# alig.net
KiCad netlist of a schematic drawn in EAGLE
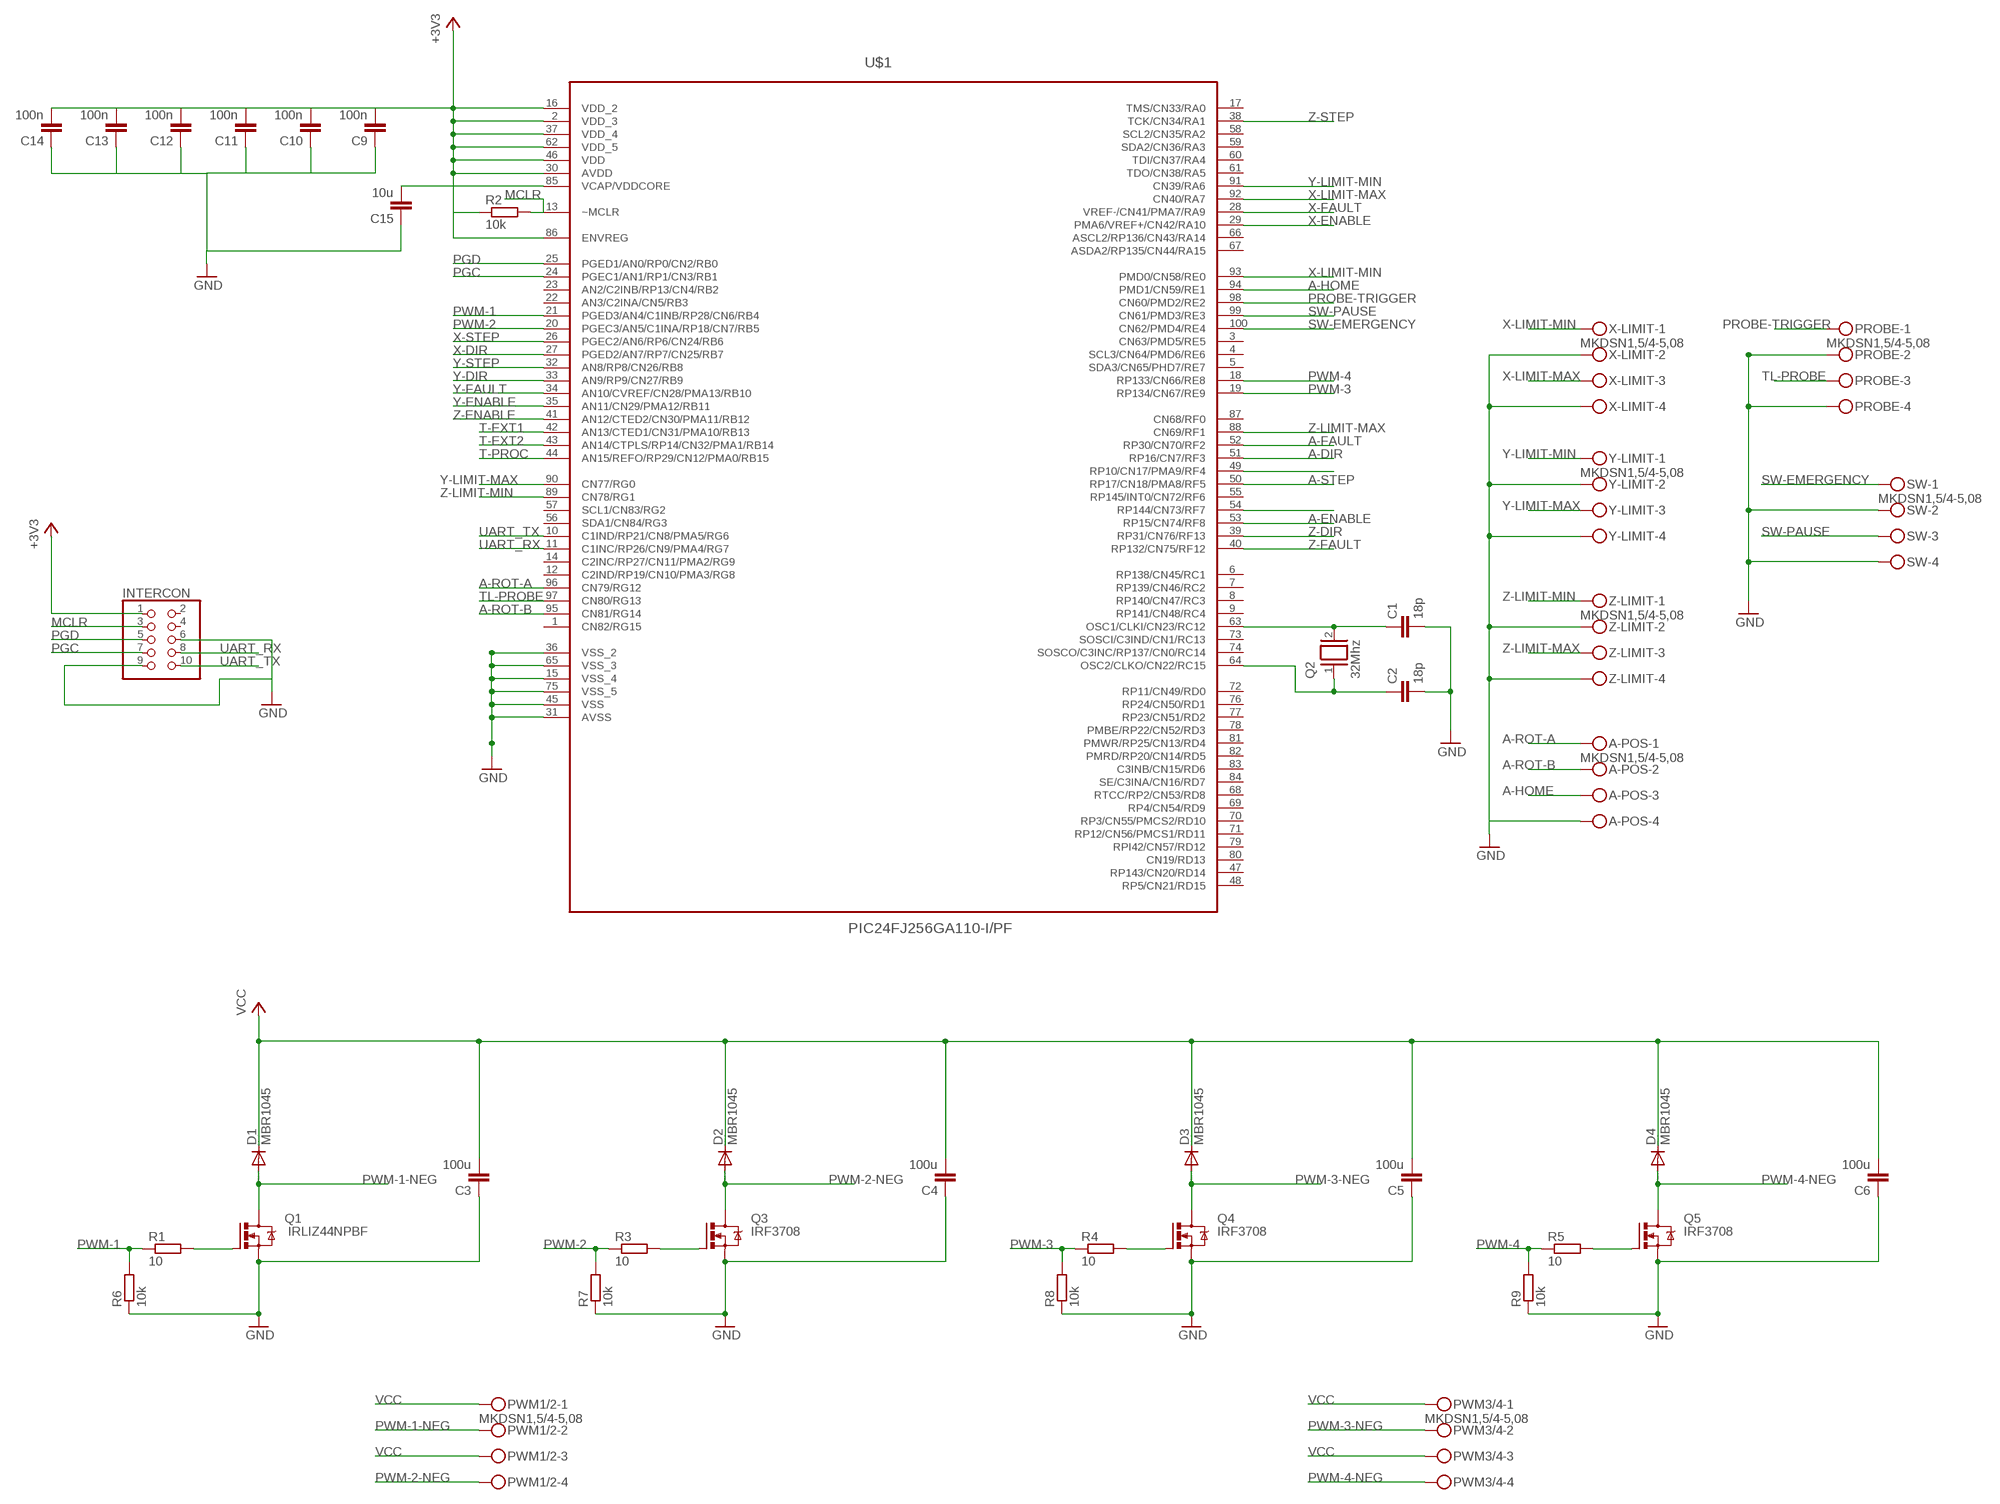
[diagram p0: schematic, sheet 1, part 1 of 3]
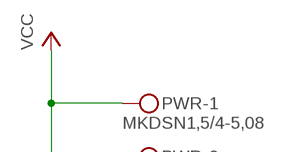
[diagram p1: schematic, sheet 1, part 2 of 3]
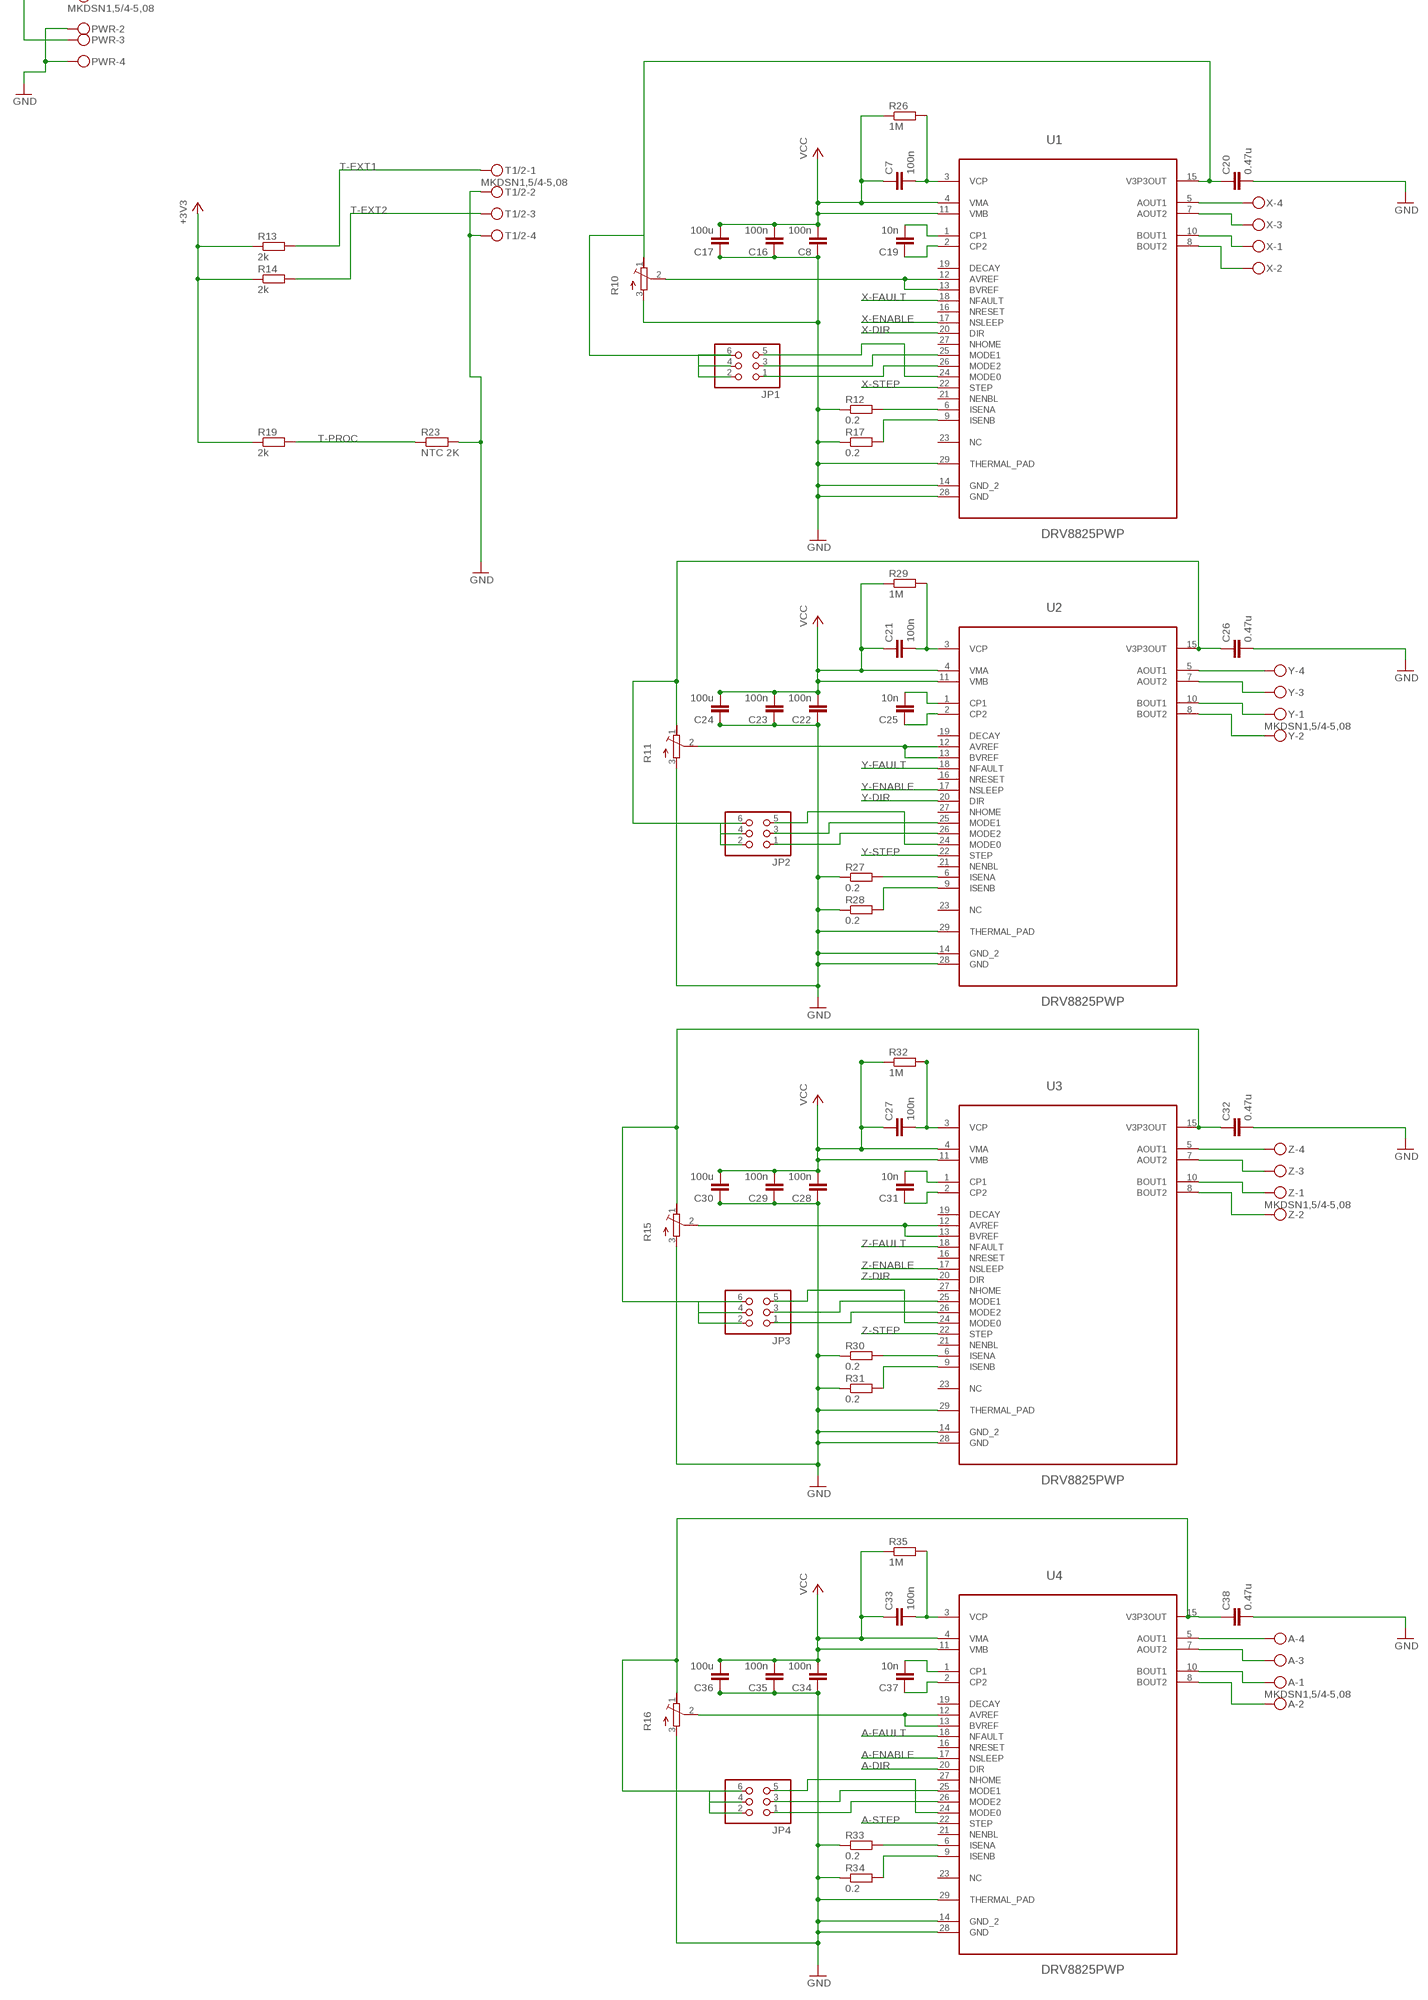
[diagram p2: schematic, sheet 1, part 3 of 3]

(export (version "E")
  (design (tool "Eeschema 10.0.6"))
  (components
    (comp (ref "A")
      (value "MKDSN1,5/4-5,08")
      (footprint "eagle-import:MKDSN1,5_4-5,08")
      (libsource (lib "eagle-import") (part "MKDSN1,5/4-5,08"))
    )
    (comp (ref "A-POS")
      (value "MKDSN1,5/4-5,08")
      (footprint "eagle-import:MKDSN1,5_4-5,08")
      (libsource (lib "eagle-import") (part "MKDSN1,5/4-5,08"))
    )
    (comp (ref "C1")
      (value "18p")
      (footprint "eagle-import:C0805")
      (libsource (lib "eagle-import") (part "C-EUC0805"))
    )
    (comp (ref "C2")
      (value "18p")
      (footprint "eagle-import:C0805")
      (libsource (lib "eagle-import") (part "C-EUC0805"))
    )
    (comp (ref "C3")
      (value "100u")
      (footprint "eagle-import:C0805")
      (libsource (lib "eagle-import") (part "C-EUC0805"))
    )
    (comp (ref "C4")
      (value "100u")
      (footprint "eagle-import:C0805")
      (libsource (lib "eagle-import") (part "C-EUC0805"))
    )
    (comp (ref "C5")
      (value "100u")
      (footprint "eagle-import:C0805")
      (libsource (lib "eagle-import") (part "C-EUC0805"))
    )
    (comp (ref "C6")
      (value "100u")
      (footprint "eagle-import:C0805")
      (libsource (lib "eagle-import") (part "C-EUC0805"))
    )
    (comp (ref "C7")
      (value "100n")
      (footprint "eagle-import:C0805")
      (libsource (lib "eagle-import") (part "C-EUC0805"))
    )
    (comp (ref "C8")
      (value "100n")
      (footprint "eagle-import:C0805")
      (libsource (lib "eagle-import") (part "C-EUC0805"))
    )
    (comp (ref "C9")
      (value "100n")
      (footprint "eagle-import:C0805")
      (libsource (lib "eagle-import") (part "C-EUC0805"))
    )
    (comp (ref "C10")
      (value "100n")
      (footprint "eagle-import:C0805")
      (libsource (lib "eagle-import") (part "C-EUC0805"))
    )
    (comp (ref "C11")
      (value "100n")
      (footprint "eagle-import:C0805")
      (libsource (lib "eagle-import") (part "C-EUC0805"))
    )
    (comp (ref "C12")
      (value "100n")
      (footprint "eagle-import:C0805")
      (libsource (lib "eagle-import") (part "C-EUC0805"))
    )
    (comp (ref "C13")
      (value "100n")
      (footprint "eagle-import:C0805")
      (libsource (lib "eagle-import") (part "C-EUC0805"))
    )
    (comp (ref "C14")
      (value "100n")
      (footprint "eagle-import:C0805")
      (libsource (lib "eagle-import") (part "C-EUC0805"))
    )
    (comp (ref "C15")
      (value "10u")
      (footprint "eagle-import:C0805")
      (libsource (lib "eagle-import") (part "C-EUC0805"))
    )
    (comp (ref "C16")
      (value "100n")
      (footprint "eagle-import:C0805")
      (libsource (lib "eagle-import") (part "C-EUC0805"))
    )
    (comp (ref "C17")
      (value "100u")
      (footprint "eagle-import:C0805")
      (libsource (lib "eagle-import") (part "C-EUC0805"))
    )
    (comp (ref "C19")
      (value "10n")
      (footprint "eagle-import:C0805")
      (libsource (lib "eagle-import") (part "C-EUC0805"))
    )
    (comp (ref "C20")
      (value "0.47u")
      (footprint "eagle-import:C0805")
      (libsource (lib "eagle-import") (part "C-EUC0805"))
    )
    (comp (ref "C21")
      (value "100n")
      (footprint "eagle-import:C0805")
      (libsource (lib "eagle-import") (part "C-EUC0805"))
    )
    (comp (ref "C22")
      (value "100n")
      (footprint "eagle-import:C0805")
      (libsource (lib "eagle-import") (part "C-EUC0805"))
    )
    (comp (ref "C23")
      (value "100n")
      (footprint "eagle-import:C0805")
      (libsource (lib "eagle-import") (part "C-EUC0805"))
    )
    (comp (ref "C24")
      (value "100u")
      (footprint "eagle-import:C0805")
      (libsource (lib "eagle-import") (part "C-EUC0805"))
    )
    (comp (ref "C25")
      (value "10n")
      (footprint "eagle-import:C0805")
      (libsource (lib "eagle-import") (part "C-EUC0805"))
    )
    (comp (ref "C26")
      (value "0.47u")
      (footprint "eagle-import:C0805")
      (libsource (lib "eagle-import") (part "C-EUC0805"))
    )
    (comp (ref "C27")
      (value "100n")
      (footprint "eagle-import:C0805")
      (libsource (lib "eagle-import") (part "C-EUC0805"))
    )
    (comp (ref "C28")
      (value "100n")
      (footprint "eagle-import:C0805")
      (libsource (lib "eagle-import") (part "C-EUC0805"))
    )
    (comp (ref "C29")
      (value "100n")
      (footprint "eagle-import:C0805")
      (libsource (lib "eagle-import") (part "C-EUC0805"))
    )
    (comp (ref "C30")
      (value "100u")
      (footprint "eagle-import:C0805")
      (libsource (lib "eagle-import") (part "C-EUC0805"))
    )
    (comp (ref "C31")
      (value "10n")
      (footprint "eagle-import:C0805")
      (libsource (lib "eagle-import") (part "C-EUC0805"))
    )
    (comp (ref "C32")
      (value "0.47u")
      (footprint "eagle-import:C0805")
      (libsource (lib "eagle-import") (part "C-EUC0805"))
    )
    (comp (ref "C33")
      (value "100n")
      (footprint "eagle-import:C0805")
      (libsource (lib "eagle-import") (part "C-EUC0805"))
    )
    (comp (ref "C34")
      (value "100n")
      (footprint "eagle-import:C0805")
      (libsource (lib "eagle-import") (part "C-EUC0805"))
    )
    (comp (ref "C35")
      (value "100n")
      (footprint "eagle-import:C0805")
      (libsource (lib "eagle-import") (part "C-EUC0805"))
    )
    (comp (ref "C36")
      (value "100u")
      (footprint "eagle-import:C0805")
      (libsource (lib "eagle-import") (part "C-EUC0805"))
    )
    (comp (ref "C37")
      (value "10n")
      (footprint "eagle-import:C0805")
      (libsource (lib "eagle-import") (part "C-EUC0805"))
    )
    (comp (ref "C38")
      (value "0.47u")
      (footprint "eagle-import:C0805")
      (libsource (lib "eagle-import") (part "C-EUC0805"))
    )
    (comp (ref "D1")
      (value "MBR1045")
      (footprint "eagle-import:TO220ACS")
      (libsource (lib "eagle-import") (part "BYT08P"))
    )
    (comp (ref "D2")
      (value "MBR1045")
      (footprint "eagle-import:TO220ACS")
      (libsource (lib "eagle-import") (part "BYT08P"))
    )
    (comp (ref "D3")
      (value "MBR1045")
      (footprint "eagle-import:TO220ACS")
      (libsource (lib "eagle-import") (part "BYT08P"))
    )
    (comp (ref "D4")
      (value "MBR1045")
      (footprint "eagle-import:TO220ACS")
      (libsource (lib "eagle-import") (part "BYT08P"))
    )
    (comp (ref "INTERCON")
      (value "PINHD-2X5")
      (footprint "eagle-import:2X05")
      (libsource (lib "eagle-import") (part "PINHD-2X5"))
    )
    (comp (ref "JP1")
      (value "PINHD-2X3")
      (footprint "eagle-import:2X03")
      (libsource (lib "eagle-import") (part "PINHD-2X3"))
    )
    (comp (ref "JP2")
      (value "PINHD-2X3")
      (footprint "eagle-import:2X03")
      (libsource (lib "eagle-import") (part "PINHD-2X3"))
    )
    (comp (ref "JP3")
      (value "PINHD-2X3")
      (footprint "eagle-import:2X03")
      (libsource (lib "eagle-import") (part "PINHD-2X3"))
    )
    (comp (ref "JP4")
      (value "PINHD-2X3")
      (footprint "eagle-import:2X03")
      (libsource (lib "eagle-import") (part "PINHD-2X3"))
    )
    (comp (ref "PROBE")
      (value "MKDSN1,5/4-5,08")
      (footprint "eagle-import:MKDSN1,5_4-5,08")
      (libsource (lib "eagle-import") (part "MKDSN1,5/4-5,08"))
    )
    (comp (ref "PWM1/2")
      (value "MKDSN1,5/4-5,08")
      (footprint "eagle-import:MKDSN1,5_4-5,08")
      (libsource (lib "eagle-import") (part "MKDSN1,5/4-5,08"))
    )
    (comp (ref "PWM3/4")
      (value "MKDSN1,5/4-5,08")
      (footprint "eagle-import:MKDSN1,5_4-5,08")
      (libsource (lib "eagle-import") (part "MKDSN1,5/4-5,08"))
    )
    (comp (ref "PWR")
      (value "MKDSN1,5/4-5,08")
      (footprint "eagle-import:MKDSN1,5_4-5,08")
      (libsource (lib "eagle-import") (part "MKDSN1,5/4-5,08"))
    )
    (comp (ref "Q1")
      (value "IRLIZ44NPBF")
      (footprint "eagle-import:TO220BV")
      (libsource (lib "eagle-import") (part "IRF540"))
    )
    (comp (ref "Q2")
      (value "32Mhz")
      (footprint "eagle-import:QS")
      (libsource (lib "eagle-import") (part "XTAL/S"))
    )
    (comp (ref "Q3")
      (value "IRF3708")
      (footprint "eagle-import:TO220BV")
      (libsource (lib "eagle-import") (part "IRF540"))
    )
    (comp (ref "Q4")
      (value "IRF3708")
      (footprint "eagle-import:TO220BV")
      (libsource (lib "eagle-import") (part "IRF540"))
    )
    (comp (ref "Q5")
      (value "IRF3708")
      (footprint "eagle-import:TO220BV")
      (libsource (lib "eagle-import") (part "IRF540"))
    )
    (comp (ref "R1")
      (value "10")
      (footprint "eagle-import:R0805")
      (libsource (lib "eagle-import") (part "resistor_R-EU_R0805"))
    )
    (comp (ref "R2")
      (value "10k")
      (footprint "eagle-import:R0805")
      (libsource (lib "eagle-import") (part "resistor_R-EU_R0805"))
    )
    (comp (ref "R3")
      (value "10")
      (footprint "eagle-import:R0805")
      (libsource (lib "eagle-import") (part "resistor_R-EU_R0805"))
    )
    (comp (ref "R4")
      (value "10")
      (footprint "eagle-import:R0805")
      (libsource (lib "eagle-import") (part "resistor_R-EU_R0805"))
    )
    (comp (ref "R5")
      (value "10")
      (footprint "eagle-import:R0805")
      (libsource (lib "eagle-import") (part "resistor_R-EU_R0805"))
    )
    (comp (ref "R6")
      (value "10k")
      (footprint "eagle-import:R0805")
      (libsource (lib "eagle-import") (part "resistor_R-EU_R0805"))
    )
    (comp (ref "R7")
      (value "10k")
      (footprint "eagle-import:R0805")
      (libsource (lib "eagle-import") (part "resistor_R-EU_R0805"))
    )
    (comp (ref "R8")
      (value "10k")
      (footprint "eagle-import:R0805")
      (libsource (lib "eagle-import") (part "resistor_R-EU_R0805"))
    )
    (comp (ref "R9")
      (value "10k")
      (footprint "eagle-import:R0805")
      (libsource (lib "eagle-import") (part "resistor_R-EU_R0805"))
    )
    (comp (ref "R10")
      (value "R-TRIMM3314J")
      (footprint "eagle-import:RTRIM3314J")
      (libsource (lib "eagle-import") (part "R-TRIMM3314J"))
    )
    (comp (ref "R11")
      (value "R-TRIMM3314J")
      (footprint "eagle-import:RTRIM3314J")
      (libsource (lib "eagle-import") (part "R-TRIMM3314J"))
    )
    (comp (ref "R12")
      (value "0.2")
      (footprint "eagle-import:R1206")
      (libsource (lib "eagle-import") (part "R-EU_R1206"))
    )
    (comp (ref "R13")
      (value "2k")
      (footprint "eagle-import:R0805")
      (libsource (lib "eagle-import") (part "resistor_R-EU_R0805"))
    )
    (comp (ref "R14")
      (value "2k")
      (footprint "eagle-import:R0805")
      (libsource (lib "eagle-import") (part "resistor_R-EU_R0805"))
    )
    (comp (ref "R15")
      (value "R-TRIMM3314J")
      (footprint "eagle-import:RTRIM3314J")
      (libsource (lib "eagle-import") (part "R-TRIMM3314J"))
    )
    (comp (ref "R16")
      (value "R-TRIMM3314J")
      (footprint "eagle-import:RTRIM3314J")
      (libsource (lib "eagle-import") (part "R-TRIMM3314J"))
    )
    (comp (ref "R17")
      (value "0.2")
      (footprint "eagle-import:R1206")
      (libsource (lib "eagle-import") (part "R-EU_R1206"))
    )
    (comp (ref "R19")
      (value "2k")
      (footprint "eagle-import:R0805")
      (libsource (lib "eagle-import") (part "resistor_R-EU_R0805"))
    )
    (comp (ref "R23")
      (value "NTC 2K")
      (footprint "eagle-import:R0805")
      (libsource (lib "eagle-import") (part "resistor_R-EU_R0805"))
    )
    (comp (ref "R26")
      (value "1M")
      (footprint "eagle-import:R0805")
      (libsource (lib "eagle-import") (part "resistor_R-EU_R0805"))
    )
    (comp (ref "R27")
      (value "0.2")
      (footprint "eagle-import:R1206")
      (libsource (lib "eagle-import") (part "R-EU_R1206"))
    )
    (comp (ref "R28")
      (value "0.2")
      (footprint "eagle-import:R1206")
      (libsource (lib "eagle-import") (part "R-EU_R1206"))
    )
    (comp (ref "R29")
      (value "1M")
      (footprint "eagle-import:R0805")
      (libsource (lib "eagle-import") (part "resistor_R-EU_R0805"))
    )
    (comp (ref "R30")
      (value "0.2")
      (footprint "eagle-import:R1206")
      (libsource (lib "eagle-import") (part "R-EU_R1206"))
    )
    (comp (ref "R31")
      (value "0.2")
      (footprint "eagle-import:R1206")
      (libsource (lib "eagle-import") (part "R-EU_R1206"))
    )
    (comp (ref "R32")
      (value "1M")
      (footprint "eagle-import:R0805")
      (libsource (lib "eagle-import") (part "resistor_R-EU_R0805"))
    )
    (comp (ref "R33")
      (value "0.2")
      (footprint "eagle-import:R1206")
      (libsource (lib "eagle-import") (part "R-EU_R1206"))
    )
    (comp (ref "R34")
      (value "0.2")
      (footprint "eagle-import:R1206")
      (libsource (lib "eagle-import") (part "R-EU_R1206"))
    )
    (comp (ref "R35")
      (value "1M")
      (footprint "eagle-import:R0805")
      (libsource (lib "eagle-import") (part "resistor_R-EU_R0805"))
    )
    (comp (ref "SW")
      (value "MKDSN1,5/4-5,08")
      (footprint "eagle-import:MKDSN1,5_4-5,08")
      (libsource (lib "eagle-import") (part "MKDSN1,5/4-5,08"))
    )
    (comp (ref "T1/2")
      (value "MKDSN1,5/4-5,08")
      (footprint "eagle-import:MKDSN1,5_4-5,08")
      (libsource (lib "eagle-import") (part "MKDSN1,5/4-5,08"))
    )
    (comp (ref "U$1")
      (value "PIC24FJ256GA110-I/PF")
      (footprint "eagle-import:QFP50P1600X1600X120-100N")
      (libsource (lib "eagle-import") (part "PIC24FJ256GA110-I/PF"))
    )
    (comp (ref "U1")
      (value "DRV8825PWP")
      (footprint "eagle-import:SOP65P640X120-29N")
      (libsource (lib "eagle-import") (part "DRV8825PWP"))
    )
    (comp (ref "U2")
      (value "DRV8825PWP")
      (footprint "eagle-import:SOP65P640X120-29N")
      (libsource (lib "eagle-import") (part "DRV8825PWP"))
    )
    (comp (ref "U3")
      (value "DRV8825PWP")
      (footprint "eagle-import:SOP65P640X120-29N")
      (libsource (lib "eagle-import") (part "DRV8825PWP"))
    )
    (comp (ref "U4")
      (value "DRV8825PWP")
      (footprint "eagle-import:SOP65P640X120-29N")
      (libsource (lib "eagle-import") (part "DRV8825PWP"))
    )
    (comp (ref "X")
      (value "MKDSN1,5/4-5,08")
      (footprint "eagle-import:MKDSN1,5_4-5,08")
      (libsource (lib "eagle-import") (part "MKDSN1,5/4-5,08"))
    )
    (comp (ref "X-LIMIT")
      (value "MKDSN1,5/4-5,08")
      (footprint "eagle-import:MKDSN1,5_4-5,08")
      (libsource (lib "eagle-import") (part "MKDSN1,5/4-5,08"))
    )
    (comp (ref "Y")
      (value "MKDSN1,5/4-5,08")
      (footprint "eagle-import:MKDSN1,5_4-5,08")
      (libsource (lib "eagle-import") (part "MKDSN1,5/4-5,08"))
    )
    (comp (ref "Y-LIMIT")
      (value "MKDSN1,5/4-5,08")
      (footprint "eagle-import:MKDSN1,5_4-5,08")
      (libsource (lib "eagle-import") (part "MKDSN1,5/4-5,08"))
    )
    (comp (ref "Z")
      (value "MKDSN1,5/4-5,08")
      (footprint "eagle-import:MKDSN1,5_4-5,08")
      (libsource (lib "eagle-import") (part "MKDSN1,5/4-5,08"))
    )
    (comp (ref "Z-LIMIT")
      (value "MKDSN1,5/4-5,08")
      (footprint "eagle-import:MKDSN1,5_4-5,08")
      (libsource (lib "eagle-import") (part "MKDSN1,5/4-5,08"))
    )
  )
  (nets
    (net (code "1") (name "+3V3") (class "Default")
      (node (ref "C10") (pin "2") (pinfunction "2_2") (pintype "passive"))
      (node (ref "C11") (pin "2") (pinfunction "2_2") (pintype "passive"))
      (node (ref "C12") (pin "2") (pinfunction "2_2") (pintype "passive"))
      (node (ref "C13") (pin "2") (pinfunction "2_2") (pintype "passive"))
      (node (ref "C14") (pin "2") (pinfunction "2_2") (pintype "passive"))
      (node (ref "C9") (pin "2") (pinfunction "2_2") (pintype "passive"))
      (node (ref "INTERCON") (pin "1") (pinfunction "1_1") (pintype "passive"))
      (node (ref "R13") (pin "1") (pinfunction "1_1") (pintype "passive"))
      (node (ref "R14") (pin "1") (pinfunction "1_1") (pintype "passive"))
      (node (ref "R19") (pin "1") (pinfunction "1_1") (pintype "passive"))
      (node (ref "R2") (pin "1") (pinfunction "1_1") (pintype "passive"))
      (node (ref "U$1") (pin "16") (pinfunction "VDD_2_16") (pintype "power_in"))
      (node (ref "U$1") (pin "2") (pinfunction "VDD_3_2") (pintype "power_in"))
      (node (ref "U$1") (pin "30") (pinfunction "AVDD_30") (pintype "power_in"))
      (node (ref "U$1") (pin "37") (pinfunction "VDD_4_37") (pintype "power_in"))
      (node (ref "U$1") (pin "46") (pinfunction "VDD_46") (pintype "power_in"))
      (node (ref "U$1") (pin "62") (pinfunction "VDD_5_62") (pintype "power_in"))
      (node (ref "U$1") (pin "86") (pinfunction "ENVREG_86") (pintype "input"))
    )
    (net (code "2") (name "/A-DIR") (class "Default")
      (node (ref "U$1") (pin "51") (pinfunction "RP16/CN7/RF3_51") (pintype "bidirectional"))
      (node (ref "U4") (pin "20") (pinfunction "DIR_20") (pintype "input"))
    )
    (net (code "3") (name "/A-ENABLE") (class "Default")
      (node (ref "U$1") (pin "53") (pinfunction "RP15/CN74/RF8_53") (pintype "bidirectional"))
      (node (ref "U4") (pin "17") (pinfunction "NSLEEP_17") (pintype "input"))
    )
    (net (code "4") (name "/A-FAULT") (class "Default")
      (node (ref "U$1") (pin "52") (pinfunction "RP30/CN70/RF2_52") (pintype "bidirectional"))
      (node (ref "U4") (pin "18") (pinfunction "NFAULT_18") (pintype "input"))
    )
    (net (code "5") (name "/A-HOME") (class "Default")
      (node (ref "A-POS") (pin "3") (pinfunction "KL_3") (pintype "passive"))
      (node (ref "U$1") (pin "94") (pinfunction "PMD1/CN59/RE1_94") (pintype "bidirectional"))
    )
    (net (code "6") (name "/A-ROT-A") (class "Default")
      (node (ref "A-POS") (pin "1") (pinfunction "KL_1") (pintype "passive"))
      (node (ref "U$1") (pin "96") (pinfunction "CN79/RG12_96") (pintype "bidirectional"))
    )
    (net (code "7") (name "/A-ROT-B") (class "Default")
      (node (ref "A-POS") (pin "2") (pinfunction "KL_2") (pintype "passive"))
      (node (ref "U$1") (pin "95") (pinfunction "CN81/RG14_95") (pintype "bidirectional"))
    )
    (net (code "8") (name "/A-STEP") (class "Default")
      (node (ref "U$1") (pin "50") (pinfunction "RP17/CN18/PMA8/RF5_50") (pintype "bidirectional"))
      (node (ref "U4") (pin "22") (pinfunction "STEP_22") (pintype "input"))
    )
    (net (code "9") (name "/MCLR") (class "Default")
      (node (ref "INTERCON") (pin "3") (pinfunction "3_3") (pintype "passive"))
      (node (ref "R2") (pin "2") (pinfunction "2_2") (pintype "passive"))
      (node (ref "U$1") (pin "13") (pinfunction "~{MCLR}_13") (pintype "input"))
    )
    (net (code "10") (name "/PGC") (class "Default")
      (node (ref "INTERCON") (pin "7") (pinfunction "7_7") (pintype "passive"))
      (node (ref "U$1") (pin "24") (pinfunction "PGEC1/AN1/RP1/CN3/RB1_24") (pintype "bidirectional"))
    )
    (net (code "11") (name "/PGD") (class "Default")
      (node (ref "INTERCON") (pin "5") (pinfunction "5_5") (pintype "passive"))
      (node (ref "U$1") (pin "25") (pinfunction "PGED1/AN0/RP0/CN2/RB0_25") (pintype "bidirectional"))
    )
    (net (code "12") (name "/PROBE-TRIGGER") (class "Default")
      (node (ref "PROBE") (pin "1") (pinfunction "KL_1") (pintype "passive"))
      (node (ref "U$1") (pin "98") (pinfunction "CN60/PMD2/RE2_98") (pintype "bidirectional"))
    )
    (net (code "13") (name "/PWM-1") (class "Default")
      (node (ref "R1") (pin "1") (pinfunction "1_1") (pintype "passive"))
      (node (ref "R6") (pin "2") (pinfunction "2_2") (pintype "passive"))
      (node (ref "U$1") (pin "21") (pinfunction "PGED3/AN4/C1INB/RP28/CN6/RB4_21") (pintype "bidirectional"))
    )
    (net (code "14") (name "/PWM-1-NEG") (class "Default")
      (node (ref "D1") (pin "A") (pinfunction "A_A") (pintype "passive"))
      (node (ref "PWM1/2") (pin "2") (pinfunction "KL_2") (pintype "passive"))
      (node (ref "Q1") (pin "D") (pinfunction "D_D") (pintype "passive"))
    )
    (net (code "15") (name "/PWM-2") (class "Default")
      (node (ref "R3") (pin "1") (pinfunction "1_1") (pintype "passive"))
      (node (ref "R7") (pin "2") (pinfunction "2_2") (pintype "passive"))
      (node (ref "U$1") (pin "20") (pinfunction "PGEC3/AN5/C1INA/RP18/CN7/RB5_20") (pintype "bidirectional"))
    )
    (net (code "16") (name "/PWM-2-NEG") (class "Default")
      (node (ref "D2") (pin "A") (pinfunction "A_A") (pintype "passive"))
      (node (ref "PWM1/2") (pin "4") (pinfunction "KL_4") (pintype "passive"))
      (node (ref "Q3") (pin "D") (pinfunction "D_D") (pintype "passive"))
    )
    (net (code "17") (name "/PWM-3") (class "Default")
      (node (ref "R4") (pin "1") (pinfunction "1_1") (pintype "passive"))
      (node (ref "R8") (pin "2") (pinfunction "2_2") (pintype "passive"))
      (node (ref "U$1") (pin "19") (pinfunction "RP134/CN67/RE9_19") (pintype "bidirectional"))
    )
    (net (code "18") (name "/PWM-3-NEG") (class "Default")
      (node (ref "D3") (pin "A") (pinfunction "A_A") (pintype "passive"))
      (node (ref "PWM3/4") (pin "2") (pinfunction "KL_2") (pintype "passive"))
      (node (ref "Q4") (pin "D") (pinfunction "D_D") (pintype "passive"))
    )
    (net (code "19") (name "/PWM-4") (class "Default")
      (node (ref "R5") (pin "1") (pinfunction "1_1") (pintype "passive"))
      (node (ref "R9") (pin "2") (pinfunction "2_2") (pintype "passive"))
      (node (ref "U$1") (pin "18") (pinfunction "RP133/CN66/RE8_18") (pintype "bidirectional"))
    )
    (net (code "20") (name "/PWM-4-NEG") (class "Default")
      (node (ref "D4") (pin "A") (pinfunction "A_A") (pintype "passive"))
      (node (ref "PWM3/4") (pin "4") (pinfunction "KL_4") (pintype "passive"))
      (node (ref "Q5") (pin "D") (pinfunction "D_D") (pintype "passive"))
    )
    (net (code "21") (name "/SW-EMERGENCY") (class "Default")
      (node (ref "SW") (pin "1") (pinfunction "KL_1") (pintype "passive"))
      (node (ref "U$1") (pin "100") (pinfunction "CN62/PMD4/RE4_100") (pintype "bidirectional"))
    )
    (net (code "22") (name "/SW-PAUSE") (class "Default")
      (node (ref "SW") (pin "3") (pinfunction "KL_3") (pintype "passive"))
      (node (ref "U$1") (pin "99") (pinfunction "CN61/PMD3/RE3_99") (pintype "bidirectional"))
    )
    (net (code "23") (name "/T-EXT1") (class "Default")
      (node (ref "R13") (pin "2") (pinfunction "2_2") (pintype "passive"))
      (node (ref "T1/2") (pin "1") (pinfunction "KL_1") (pintype "passive"))
      (node (ref "U$1") (pin "42") (pinfunction "AN13/CTED1/CN31/PMA10/RB13_42") (pintype "bidirectional"))
    )
    (net (code "24") (name "/T-EXT2") (class "Default")
      (node (ref "R14") (pin "2") (pinfunction "2_2") (pintype "passive"))
      (node (ref "T1/2") (pin "3") (pinfunction "KL_3") (pintype "passive"))
      (node (ref "U$1") (pin "43") (pinfunction "AN14/CTPLS/RP14/CN32/PMA1/RB14_43") (pintype "bidirectional"))
    )
    (net (code "25") (name "/T-PROC") (class "Default")
      (node (ref "R19") (pin "2") (pinfunction "2_2") (pintype "passive"))
      (node (ref "R23") (pin "1") (pinfunction "1_1") (pintype "passive"))
      (node (ref "U$1") (pin "44") (pinfunction "AN15/REFO/RP29/CN12/PMA0/RB15_44") (pintype "bidirectional"))
    )
    (net (code "26") (name "/TL-PROBE") (class "Default")
      (node (ref "PROBE") (pin "3") (pinfunction "KL_3") (pintype "passive"))
      (node (ref "U$1") (pin "97") (pinfunction "CN80/RG13_97") (pintype "bidirectional"))
    )
    (net (code "27") (name "/UART_RX") (class "Default")
      (node (ref "INTERCON") (pin "8") (pinfunction "8_8") (pintype "passive"))
      (node (ref "U$1") (pin "11") (pinfunction "C1INC/RP26/CN9/PMA4/RG7_11") (pintype "bidirectional"))
    )
    (net (code "28") (name "/UART_TX") (class "Default")
      (node (ref "INTERCON") (pin "10") (pinfunction "10_10") (pintype "passive"))
      (node (ref "U$1") (pin "10") (pinfunction "C1IND/RP21/CN8/PMA5/RG6_10") (pintype "bidirectional"))
    )
    (net (code "29") (name "/X-DIR") (class "Default")
      (node (ref "U$1") (pin "27") (pinfunction "PGED2/AN7/RP7/CN25/RB7_27") (pintype "bidirectional"))
      (node (ref "U1") (pin "20") (pinfunction "DIR_20") (pintype "input"))
    )
    (net (code "30") (name "/X-ENABLE") (class "Default")
      (node (ref "U$1") (pin "29") (pinfunction "PMA6/VREF+/CN42/RA10_29") (pintype "bidirectional"))
      (node (ref "U1") (pin "17") (pinfunction "NSLEEP_17") (pintype "input"))
    )
    (net (code "31") (name "/X-FAULT") (class "Default")
      (node (ref "U$1") (pin "28") (pinfunction "VREF-/CN41/PMA7/RA9_28") (pintype "bidirectional"))
      (node (ref "U1") (pin "18") (pinfunction "NFAULT_18") (pintype "input"))
    )
    (net (code "32") (name "/X-LIMIT-MAX") (class "Default")
      (node (ref "U$1") (pin "92") (pinfunction "CN40/RA7_92") (pintype "bidirectional"))
      (node (ref "X-LIMIT") (pin "3") (pinfunction "KL_3") (pintype "passive"))
    )
    (net (code "33") (name "/X-LIMIT-MIN") (class "Default")
      (node (ref "U$1") (pin "93") (pinfunction "PMD0/CN58/RE0_93") (pintype "bidirectional"))
      (node (ref "X-LIMIT") (pin "1") (pinfunction "KL_1") (pintype "passive"))
    )
    (net (code "34") (name "/X-STEP") (class "Default")
      (node (ref "U$1") (pin "26") (pinfunction "PGEC2/AN6/RP6/CN24/RB6_26") (pintype "bidirectional"))
      (node (ref "U1") (pin "22") (pinfunction "STEP_22") (pintype "input"))
    )
    (net (code "35") (name "/Y-DIR") (class "Default")
      (node (ref "U$1") (pin "33") (pinfunction "AN9/RP9/CN27/RB9_33") (pintype "bidirectional"))
      (node (ref "U2") (pin "20") (pinfunction "DIR_20") (pintype "input"))
    )
    (net (code "36") (name "/Y-ENABLE") (class "Default")
      (node (ref "U$1") (pin "35") (pinfunction "AN11/CN29/PMA12/RB11_35") (pintype "bidirectional"))
      (node (ref "U2") (pin "17") (pinfunction "NSLEEP_17") (pintype "input"))
    )
    (net (code "37") (name "/Y-FAULT") (class "Default")
      (node (ref "U$1") (pin "34") (pinfunction "AN10/CVREF/CN28/PMA13/RB10_34") (pintype "bidirectional"))
      (node (ref "U2") (pin "18") (pinfunction "NFAULT_18") (pintype "input"))
    )
    (net (code "38") (name "/Y-LIMIT-MAX") (class "Default")
      (node (ref "U$1") (pin "90") (pinfunction "CN77/RG0_90") (pintype "bidirectional"))
      (node (ref "Y-LIMIT") (pin "3") (pinfunction "KL_3") (pintype "passive"))
    )
    (net (code "39") (name "/Y-LIMIT-MIN") (class "Default")
      (node (ref "U$1") (pin "91") (pinfunction "CN39/RA6_91") (pintype "bidirectional"))
      (node (ref "Y-LIMIT") (pin "1") (pinfunction "KL_1") (pintype "passive"))
    )
    (net (code "40") (name "/Y-STEP") (class "Default")
      (node (ref "U$1") (pin "32") (pinfunction "AN8/RP8/CN26/RB8_32") (pintype "bidirectional"))
      (node (ref "U2") (pin "22") (pinfunction "STEP_22") (pintype "input"))
    )
    (net (code "41") (name "/Z-DIR") (class "Default")
      (node (ref "U$1") (pin "39") (pinfunction "RP31/CN76/RF13_39") (pintype "bidirectional"))
      (node (ref "U3") (pin "20") (pinfunction "DIR_20") (pintype "input"))
    )
    (net (code "42") (name "/Z-ENABLE") (class "Default")
      (node (ref "U$1") (pin "41") (pinfunction "AN12/CTED2/CN30/PMA11/RB12_41") (pintype "bidirectional"))
      (node (ref "U3") (pin "17") (pinfunction "NSLEEP_17") (pintype "input"))
    )
    (net (code "43") (name "/Z-FAULT") (class "Default")
      (node (ref "U$1") (pin "40") (pinfunction "RP132/CN75/RF12_40") (pintype "bidirectional"))
      (node (ref "U3") (pin "18") (pinfunction "NFAULT_18") (pintype "input"))
    )
    (net (code "44") (name "/Z-LIMIT-MAX") (class "Default")
      (node (ref "U$1") (pin "88") (pinfunction "CN69/RF1_88") (pintype "bidirectional"))
      (node (ref "Z-LIMIT") (pin "3") (pinfunction "KL_3") (pintype "passive"))
    )
    (net (code "45") (name "/Z-LIMIT-MIN") (class "Default")
      (node (ref "U$1") (pin "89") (pinfunction "CN78/RG1_89") (pintype "bidirectional"))
      (node (ref "Z-LIMIT") (pin "1") (pinfunction "KL_1") (pintype "passive"))
    )
    (net (code "46") (name "/Z-STEP") (class "Default")
      (node (ref "U$1") (pin "38") (pinfunction "TCK/CN34/RA1_38") (pintype "bidirectional"))
      (node (ref "U3") (pin "22") (pinfunction "STEP_22") (pintype "input"))
    )
    (net (code "47") (name "GND") (class "Default")
      (node (ref "A-POS") (pin "4") (pinfunction "KL_4") (pintype "passive"))
      (node (ref "C1") (pin "2") (pinfunction "2_2") (pintype "passive"))
      (node (ref "C10") (pin "1") (pinfunction "1_1") (pintype "passive"))
      (node (ref "C11") (pin "1") (pinfunction "1_1") (pintype "passive"))
      (node (ref "C12") (pin "1") (pinfunction "1_1") (pintype "passive"))
      (node (ref "C13") (pin "1") (pinfunction "1_1") (pintype "passive"))
      (node (ref "C14") (pin "1") (pinfunction "1_1") (pintype "passive"))
      (node (ref "C15") (pin "1") (pinfunction "1_1") (pintype "passive"))
      (node (ref "C16") (pin "1") (pinfunction "1_1") (pintype "passive"))
      (node (ref "C17") (pin "1") (pinfunction "1_1") (pintype "passive"))
      (node (ref "C2") (pin "2") (pinfunction "2_2") (pintype "passive"))
      (node (ref "C20") (pin "2") (pinfunction "2_2") (pintype "passive"))
      (node (ref "C22") (pin "1") (pinfunction "1_1") (pintype "passive"))
      (node (ref "C23") (pin "1") (pinfunction "1_1") (pintype "passive"))
      (node (ref "C24") (pin "1") (pinfunction "1_1") (pintype "passive"))
      (node (ref "C26") (pin "2") (pinfunction "2_2") (pintype "passive"))
      (node (ref "C28") (pin "1") (pinfunction "1_1") (pintype "passive"))
      (node (ref "C29") (pin "1") (pinfunction "1_1") (pintype "passive"))
      (node (ref "C3") (pin "1") (pinfunction "1_1") (pintype "passive"))
      (node (ref "C30") (pin "1") (pinfunction "1_1") (pintype "passive"))
      (node (ref "C32") (pin "2") (pinfunction "2_2") (pintype "passive"))
      (node (ref "C34") (pin "1") (pinfunction "1_1") (pintype "passive"))
      (node (ref "C35") (pin "1") (pinfunction "1_1") (pintype "passive"))
      (node (ref "C36") (pin "1") (pinfunction "1_1") (pintype "passive"))
      (node (ref "C38") (pin "2") (pinfunction "2_2") (pintype "passive"))
      (node (ref "C4") (pin "1") (pinfunction "1_1") (pintype "passive"))
      (node (ref "C5") (pin "1") (pinfunction "1_1") (pintype "passive"))
      (node (ref "C6") (pin "1") (pinfunction "1_1") (pintype "passive"))
      (node (ref "C8") (pin "1") (pinfunction "1_1") (pintype "passive"))
      (node (ref "C9") (pin "1") (pinfunction "1_1") (pintype "passive"))
      (node (ref "INTERCON") (pin "6") (pinfunction "6_6") (pintype "passive"))
      (node (ref "INTERCON") (pin "9") (pinfunction "9_9") (pintype "passive"))
      (node (ref "PROBE") (pin "2") (pinfunction "KL_2") (pintype "passive"))
      (node (ref "PROBE") (pin "4") (pinfunction "KL_4") (pintype "passive"))
      (node (ref "PWR") (pin "2") (pinfunction "KL_2") (pintype "passive"))
      (node (ref "PWR") (pin "4") (pinfunction "KL_4") (pintype "passive"))
      (node (ref "Q1") (pin "S") (pinfunction "S_S") (pintype "passive"))
      (node (ref "Q3") (pin "S") (pinfunction "S_S") (pintype "passive"))
      (node (ref "Q4") (pin "S") (pinfunction "S_S") (pintype "passive"))
      (node (ref "Q5") (pin "S") (pinfunction "S_S") (pintype "passive"))
      (node (ref "R10") (pin "3") (pinfunction "A_3") (pintype "passive"))
      (node (ref "R11") (pin "3") (pinfunction "A_3") (pintype "passive"))
      (node (ref "R12") (pin "1") (pinfunction "1_1") (pintype "passive"))
      (node (ref "R15") (pin "3") (pinfunction "A_3") (pintype "passive"))
      (node (ref "R16") (pin "3") (pinfunction "A_3") (pintype "passive"))
      (node (ref "R17") (pin "1") (pinfunction "1_1") (pintype "passive"))
      (node (ref "R23") (pin "2") (pinfunction "2_2") (pintype "passive"))
      (node (ref "R27") (pin "1") (pinfunction "1_1") (pintype "passive"))
      (node (ref "R28") (pin "1") (pinfunction "1_1") (pintype "passive"))
      (node (ref "R30") (pin "1") (pinfunction "1_1") (pintype "passive"))
      (node (ref "R31") (pin "1") (pinfunction "1_1") (pintype "passive"))
      (node (ref "R33") (pin "1") (pinfunction "1_1") (pintype "passive"))
      (node (ref "R34") (pin "1") (pinfunction "1_1") (pintype "passive"))
      (node (ref "R6") (pin "1") (pinfunction "1_1") (pintype "passive"))
      (node (ref "R7") (pin "1") (pinfunction "1_1") (pintype "passive"))
      (node (ref "R8") (pin "1") (pinfunction "1_1") (pintype "passive"))
      (node (ref "R9") (pin "1") (pinfunction "1_1") (pintype "passive"))
      (node (ref "SW") (pin "2") (pinfunction "KL_2") (pintype "passive"))
      (node (ref "SW") (pin "4") (pinfunction "KL_4") (pintype "passive"))
      (node (ref "T1/2") (pin "2") (pinfunction "KL_2") (pintype "passive"))
      (node (ref "T1/2") (pin "4") (pinfunction "KL_4") (pintype "passive"))
      (node (ref "U$1") (pin "15") (pinfunction "VSS_4_15") (pintype "passive"))
      (node (ref "U$1") (pin "31") (pinfunction "AVSS_31") (pintype "passive"))
      (node (ref "U$1") (pin "36") (pinfunction "VSS_2_36") (pintype "passive"))
      (node (ref "U$1") (pin "45") (pinfunction "VSS_45") (pintype "passive"))
      (node (ref "U$1") (pin "65") (pinfunction "VSS_3_65") (pintype "passive"))
      (node (ref "U$1") (pin "75") (pinfunction "VSS_5_75") (pintype "passive"))
      (node (ref "U1") (pin "14") (pinfunction "GND_2_14") (pintype "passive"))
      (node (ref "U1") (pin "28") (pinfunction "GND_28") (pintype "passive"))
      (node (ref "U1") (pin "29") (pinfunction "THERMAL_PAD_29") (pintype "passive"))
      (node (ref "U2") (pin "14") (pinfunction "GND_2_14") (pintype "passive"))
      (node (ref "U2") (pin "28") (pinfunction "GND_28") (pintype "passive"))
      (node (ref "U2") (pin "29") (pinfunction "THERMAL_PAD_29") (pintype "passive"))
      (node (ref "U3") (pin "14") (pinfunction "GND_2_14") (pintype "passive"))
      (node (ref "U3") (pin "28") (pinfunction "GND_28") (pintype "passive"))
      (node (ref "U3") (pin "29") (pinfunction "THERMAL_PAD_29") (pintype "passive"))
      (node (ref "U4") (pin "14") (pinfunction "GND_2_14") (pintype "passive"))
      (node (ref "U4") (pin "28") (pinfunction "GND_28") (pintype "passive"))
      (node (ref "U4") (pin "29") (pinfunction "THERMAL_PAD_29") (pintype "passive"))
      (node (ref "X-LIMIT") (pin "2") (pinfunction "KL_2") (pintype "passive"))
      (node (ref "X-LIMIT") (pin "4") (pinfunction "KL_4") (pintype "passive"))
      (node (ref "Y-LIMIT") (pin "2") (pinfunction "KL_2") (pintype "passive"))
      (node (ref "Y-LIMIT") (pin "4") (pinfunction "KL_4") (pintype "passive"))
      (node (ref "Z-LIMIT") (pin "2") (pinfunction "KL_2") (pintype "passive"))
      (node (ref "Z-LIMIT") (pin "4") (pinfunction "KL_4") (pintype "passive"))
    )
    (net (code "48") (name "Net-(AA-KL)") (class "Default")
      (node (ref "A") (pin "1") (pinfunction "KL_1") (pintype "passive"))
      (node (ref "U4") (pin "10") (pinfunction "BOUT1_10") (pintype "output"))
    )
    (net (code "49") (name "Net-(AB-KL)") (class "Default")
      (node (ref "A") (pin "2") (pinfunction "KL_2") (pintype "passive"))
      (node (ref "U4") (pin "8") (pinfunction "BOUT2_8") (pintype "output"))
    )
    (net (code "50") (name "Net-(AC-KL)") (class "Default")
      (node (ref "A") (pin "3") (pinfunction "KL_3") (pintype "passive"))
      (node (ref "U4") (pin "7") (pinfunction "AOUT2_7") (pintype "output"))
    )
    (net (code "51") (name "Net-(AD-KL)") (class "Default")
      (node (ref "A") (pin "4") (pinfunction "KL_4") (pintype "passive"))
      (node (ref "U4") (pin "5") (pinfunction "AOUT1_5") (pintype "output"))
    )
    (net (code "52") (name "Net-(Q1-PadG)") (class "Default")
      (node (ref "Q1") (pin "G") (pinfunction "G_G") (pintype "passive"))
      (node (ref "R1") (pin "2") (pinfunction "2_2") (pintype "passive"))
    )
    (net (code "53") (name "Net-(Q3-PadG)") (class "Default")
      (node (ref "Q3") (pin "G") (pinfunction "G_G") (pintype "passive"))
      (node (ref "R3") (pin "2") (pinfunction "2_2") (pintype "passive"))
    )
    (net (code "54") (name "Net-(Q4-PadG)") (class "Default")
      (node (ref "Q4") (pin "G") (pinfunction "G_G") (pintype "passive"))
      (node (ref "R4") (pin "2") (pinfunction "2_2") (pintype "passive"))
    )
    (net (code "55") (name "Net-(Q5-PadG)") (class "Default")
      (node (ref "Q5") (pin "G") (pinfunction "G_G") (pintype "passive"))
      (node (ref "R5") (pin "2") (pinfunction "2_2") (pintype "passive"))
    )
    (net (code "56") (name "Net-(R10-E)") (class "Default")
      (node (ref "C20") (pin "1") (pinfunction "1_1") (pintype "passive"))
      (node (ref "JP1") (pin "2") (pinfunction "2_2") (pintype "passive"))
      (node (ref "JP1") (pin "4") (pinfunction "4_4") (pintype "passive"))
      (node (ref "JP1") (pin "6") (pinfunction "6_6") (pintype "passive"))
      (node (ref "R10") (pin "1") (pinfunction "E_1") (pintype "passive"))
      (node (ref "U1") (pin "15") (pinfunction "V3P3OUT_15") (pintype "output"))
    )
    (net (code "57") (name "Net-(R10-S)") (class "Default")
      (node (ref "R10") (pin "2") (pinfunction "S_2") (pintype "passive"))
      (node (ref "U1") (pin "12") (pinfunction "AVREF_12") (pintype "input"))
      (node (ref "U1") (pin "13") (pinfunction "BVREF_13") (pintype "input"))
    )
    (net (code "58") (name "Net-(R11-E)") (class "Default")
      (node (ref "C26") (pin "1") (pinfunction "1_1") (pintype "passive"))
      (node (ref "JP2") (pin "2") (pinfunction "2_2") (pintype "passive"))
      (node (ref "JP2") (pin "4") (pinfunction "4_4") (pintype "passive"))
      (node (ref "JP2") (pin "6") (pinfunction "6_6") (pintype "passive"))
      (node (ref "R11") (pin "1") (pinfunction "E_1") (pintype "passive"))
      (node (ref "U2") (pin "15") (pinfunction "V3P3OUT_15") (pintype "output"))
    )
    (net (code "59") (name "Net-(R11-S)") (class "Default")
      (node (ref "R11") (pin "2") (pinfunction "S_2") (pintype "passive"))
      (node (ref "U2") (pin "12") (pinfunction "AVREF_12") (pintype "input"))
      (node (ref "U2") (pin "13") (pinfunction "BVREF_13") (pintype "input"))
    )
    (net (code "60") (name "Net-(R15-E)") (class "Default")
      (node (ref "C32") (pin "1") (pinfunction "1_1") (pintype "passive"))
      (node (ref "JP3") (pin "2") (pinfunction "2_2") (pintype "passive"))
      (node (ref "JP3") (pin "4") (pinfunction "4_4") (pintype "passive"))
      (node (ref "JP3") (pin "6") (pinfunction "6_6") (pintype "passive"))
      (node (ref "R15") (pin "1") (pinfunction "E_1") (pintype "passive"))
      (node (ref "U3") (pin "15") (pinfunction "V3P3OUT_15") (pintype "output"))
    )
    (net (code "61") (name "Net-(R15-S)") (class "Default")
      (node (ref "R15") (pin "2") (pinfunction "S_2") (pintype "passive"))
      (node (ref "U3") (pin "12") (pinfunction "AVREF_12") (pintype "input"))
      (node (ref "U3") (pin "13") (pinfunction "BVREF_13") (pintype "input"))
    )
    (net (code "62") (name "Net-(R16-E)") (class "Default")
      (node (ref "C38") (pin "1") (pinfunction "1_1") (pintype "passive"))
      (node (ref "JP4") (pin "2") (pinfunction "2_2") (pintype "passive"))
      (node (ref "JP4") (pin "4") (pinfunction "4_4") (pintype "passive"))
      (node (ref "JP4") (pin "6") (pinfunction "6_6") (pintype "passive"))
      (node (ref "R16") (pin "1") (pinfunction "E_1") (pintype "passive"))
      (node (ref "U4") (pin "15") (pinfunction "V3P3OUT_15") (pintype "output"))
    )
    (net (code "63") (name "Net-(R16-S)") (class "Default")
      (node (ref "R16") (pin "2") (pinfunction "S_2") (pintype "passive"))
      (node (ref "U4") (pin "12") (pinfunction "AVREF_12") (pintype "input"))
      (node (ref "U4") (pin "13") (pinfunction "BVREF_13") (pintype "input"))
    )
    (net (code "64") (name "Net-(U$1-OSC1{slash}CLKI{slash}CN23{slash}RC12)") (class "Default")
      (node (ref "C1") (pin "1") (pinfunction "1_1") (pintype "passive"))
      (node (ref "Q2") (pin "2") (pinfunction "2_2") (pintype "passive"))
      (node (ref "U$1") (pin "63") (pinfunction "OSC1/CLKI/CN23/RC12_63") (pintype "bidirectional"))
    )
    (net (code "65") (name "Net-(U$1-OSC2{slash}CLKO{slash}CN22{slash}RC15)") (class "Default")
      (node (ref "C2") (pin "1") (pinfunction "1_1") (pintype "passive"))
      (node (ref "Q2") (pin "1") (pinfunction "1_1") (pintype "passive"))
      (node (ref "U$1") (pin "64") (pinfunction "OSC2/CLKO/CN22/RC15_64") (pintype "bidirectional"))
    )
    (net (code "66") (name "Net-(U$1-VCAP{slash}VDDCORE)") (class "Default")
      (node (ref "C15") (pin "2") (pinfunction "2_2") (pintype "passive"))
      (node (ref "U$1") (pin "85") (pinfunction "VCAP/VDDCORE_85") (pintype "power_in"))
    )
    (net (code "67") (name "Net-(U1-AOUT1)") (class "Default")
      (node (ref "U1") (pin "5") (pinfunction "AOUT1_5") (pintype "output"))
      (node (ref "X") (pin "4") (pinfunction "KL_4") (pintype "passive"))
    )
    (net (code "68") (name "Net-(U1-AOUT2)") (class "Default")
      (node (ref "U1") (pin "7") (pinfunction "AOUT2_7") (pintype "output"))
      (node (ref "X") (pin "3") (pinfunction "KL_3") (pintype "passive"))
    )
    (net (code "69") (name "Net-(U1-BOUT1)") (class "Default")
      (node (ref "U1") (pin "10") (pinfunction "BOUT1_10") (pintype "output"))
      (node (ref "X") (pin "1") (pinfunction "KL_1") (pintype "passive"))
    )
    (net (code "70") (name "Net-(U1-BOUT2)") (class "Default")
      (node (ref "U1") (pin "8") (pinfunction "BOUT2_8") (pintype "output"))
      (node (ref "X") (pin "2") (pinfunction "KL_2") (pintype "passive"))
    )
    (net (code "71") (name "Net-(U1-CP1)") (class "Default")
      (node (ref "C19") (pin "2") (pinfunction "2_2") (pintype "passive"))
      (node (ref "U1") (pin "1") (pinfunction "CP1_1") (pintype "bidirectional"))
    )
    (net (code "72") (name "Net-(U1-CP2)") (class "Default")
      (node (ref "C19") (pin "1") (pinfunction "1_1") (pintype "passive"))
      (node (ref "U1") (pin "2") (pinfunction "CP2_2") (pintype "bidirectional"))
    )
    (net (code "73") (name "Net-(U1-ISENA)") (class "Default")
      (node (ref "R12") (pin "2") (pinfunction "2_2") (pintype "passive"))
      (node (ref "U1") (pin "6") (pinfunction "ISENA_6") (pintype "bidirectional"))
    )
    (net (code "74") (name "Net-(U1-ISENB)") (class "Default")
      (node (ref "R17") (pin "2") (pinfunction "2_2") (pintype "passive"))
      (node (ref "U1") (pin "9") (pinfunction "ISENB_9") (pintype "bidirectional"))
    )
    (net (code "75") (name "Net-(U1-MODE0)") (class "Default")
      (node (ref "JP1") (pin "5") (pinfunction "5_5") (pintype "passive"))
      (node (ref "U1") (pin "24") (pinfunction "MODE0_24") (pintype "input"))
    )
    (net (code "76") (name "Net-(U1-MODE1)") (class "Default")
      (node (ref "JP1") (pin "3") (pinfunction "3_3") (pintype "passive"))
      (node (ref "U1") (pin "25") (pinfunction "MODE1_25") (pintype "input"))
    )
    (net (code "77") (name "Net-(U1-MODE2)") (class "Default")
      (node (ref "JP1") (pin "1") (pinfunction "1_1") (pintype "passive"))
      (node (ref "U1") (pin "26") (pinfunction "MODE2_26") (pintype "input"))
    )
    (net (code "78") (name "Net-(U1-VCP)") (class "Default")
      (node (ref "C7") (pin "2") (pinfunction "2_2") (pintype "passive"))
      (node (ref "R26") (pin "2") (pinfunction "2_2") (pintype "passive"))
      (node (ref "U1") (pin "3") (pinfunction "VCP_3") (pintype "bidirectional"))
    )
    (net (code "79") (name "Net-(U2-AOUT1)") (class "Default")
      (node (ref "U2") (pin "5") (pinfunction "AOUT1_5") (pintype "output"))
      (node (ref "Y") (pin "4") (pinfunction "KL_4") (pintype "passive"))
    )
    (net (code "80") (name "Net-(U2-AOUT2)") (class "Default")
      (node (ref "U2") (pin "7") (pinfunction "AOUT2_7") (pintype "output"))
      (node (ref "Y") (pin "3") (pinfunction "KL_3") (pintype "passive"))
    )
    (net (code "81") (name "Net-(U2-BOUT1)") (class "Default")
      (node (ref "U2") (pin "10") (pinfunction "BOUT1_10") (pintype "output"))
      (node (ref "Y") (pin "1") (pinfunction "KL_1") (pintype "passive"))
    )
    (net (code "82") (name "Net-(U2-BOUT2)") (class "Default")
      (node (ref "U2") (pin "8") (pinfunction "BOUT2_8") (pintype "output"))
      (node (ref "Y") (pin "2") (pinfunction "KL_2") (pintype "passive"))
    )
    (net (code "83") (name "Net-(U2-CP1)") (class "Default")
      (node (ref "C25") (pin "2") (pinfunction "2_2") (pintype "passive"))
      (node (ref "U2") (pin "1") (pinfunction "CP1_1") (pintype "bidirectional"))
    )
    (net (code "84") (name "Net-(U2-CP2)") (class "Default")
      (node (ref "C25") (pin "1") (pinfunction "1_1") (pintype "passive"))
      (node (ref "U2") (pin "2") (pinfunction "CP2_2") (pintype "bidirectional"))
    )
    (net (code "85") (name "Net-(U2-ISENA)") (class "Default")
      (node (ref "R27") (pin "2") (pinfunction "2_2") (pintype "passive"))
      (node (ref "U2") (pin "6") (pinfunction "ISENA_6") (pintype "bidirectional"))
    )
    (net (code "86") (name "Net-(U2-ISENB)") (class "Default")
      (node (ref "R28") (pin "2") (pinfunction "2_2") (pintype "passive"))
      (node (ref "U2") (pin "9") (pinfunction "ISENB_9") (pintype "bidirectional"))
    )
    (net (code "87") (name "Net-(U2-MODE0)") (class "Default")
      (node (ref "JP2") (pin "5") (pinfunction "5_5") (pintype "passive"))
      (node (ref "U2") (pin "24") (pinfunction "MODE0_24") (pintype "input"))
    )
    (net (code "88") (name "Net-(U2-MODE1)") (class "Default")
      (node (ref "JP2") (pin "3") (pinfunction "3_3") (pintype "passive"))
      (node (ref "U2") (pin "25") (pinfunction "MODE1_25") (pintype "input"))
    )
    (net (code "89") (name "Net-(U2-MODE2)") (class "Default")
      (node (ref "JP2") (pin "1") (pinfunction "1_1") (pintype "passive"))
      (node (ref "U2") (pin "26") (pinfunction "MODE2_26") (pintype "input"))
    )
    (net (code "90") (name "Net-(U2-VCP)") (class "Default")
      (node (ref "C21") (pin "2") (pinfunction "2_2") (pintype "passive"))
      (node (ref "R29") (pin "2") (pinfunction "2_2") (pintype "passive"))
      (node (ref "U2") (pin "3") (pinfunction "VCP_3") (pintype "bidirectional"))
    )
    (net (code "91") (name "Net-(U3-AOUT1)") (class "Default")
      (node (ref "U3") (pin "5") (pinfunction "AOUT1_5") (pintype "output"))
      (node (ref "Z") (pin "4") (pinfunction "KL_4") (pintype "passive"))
    )
    (net (code "92") (name "Net-(U3-AOUT2)") (class "Default")
      (node (ref "U3") (pin "7") (pinfunction "AOUT2_7") (pintype "output"))
      (node (ref "Z") (pin "3") (pinfunction "KL_3") (pintype "passive"))
    )
    (net (code "93") (name "Net-(U3-BOUT1)") (class "Default")
      (node (ref "U3") (pin "10") (pinfunction "BOUT1_10") (pintype "output"))
      (node (ref "Z") (pin "1") (pinfunction "KL_1") (pintype "passive"))
    )
    (net (code "94") (name "Net-(U3-BOUT2)") (class "Default")
      (node (ref "U3") (pin "8") (pinfunction "BOUT2_8") (pintype "output"))
      (node (ref "Z") (pin "2") (pinfunction "KL_2") (pintype "passive"))
    )
    (net (code "95") (name "Net-(U3-CP1)") (class "Default")
      (node (ref "C31") (pin "2") (pinfunction "2_2") (pintype "passive"))
      (node (ref "U3") (pin "1") (pinfunction "CP1_1") (pintype "bidirectional"))
    )
    (net (code "96") (name "Net-(U3-CP2)") (class "Default")
      (node (ref "C31") (pin "1") (pinfunction "1_1") (pintype "passive"))
      (node (ref "U3") (pin "2") (pinfunction "CP2_2") (pintype "bidirectional"))
    )
    (net (code "97") (name "Net-(U3-ISENA)") (class "Default")
      (node (ref "R30") (pin "2") (pinfunction "2_2") (pintype "passive"))
      (node (ref "U3") (pin "6") (pinfunction "ISENA_6") (pintype "bidirectional"))
    )
    (net (code "98") (name "Net-(U3-ISENB)") (class "Default")
      (node (ref "R31") (pin "2") (pinfunction "2_2") (pintype "passive"))
      (node (ref "U3") (pin "9") (pinfunction "ISENB_9") (pintype "bidirectional"))
    )
    (net (code "99") (name "Net-(U3-MODE0)") (class "Default")
      (node (ref "JP3") (pin "5") (pinfunction "5_5") (pintype "passive"))
      (node (ref "U3") (pin "24") (pinfunction "MODE0_24") (pintype "input"))
    )
    (net (code "100") (name "Net-(U3-MODE1)") (class "Default")
      (node (ref "JP3") (pin "3") (pinfunction "3_3") (pintype "passive"))
      (node (ref "U3") (pin "25") (pinfunction "MODE1_25") (pintype "input"))
    )
    (net (code "101") (name "Net-(U3-MODE2)") (class "Default")
      (node (ref "JP3") (pin "1") (pinfunction "1_1") (pintype "passive"))
      (node (ref "U3") (pin "26") (pinfunction "MODE2_26") (pintype "input"))
    )
    (net (code "102") (name "Net-(U3-VCP)") (class "Default")
      (node (ref "C27") (pin "2") (pinfunction "2_2") (pintype "passive"))
      (node (ref "R32") (pin "2") (pinfunction "2_2") (pintype "passive"))
      (node (ref "U3") (pin "3") (pinfunction "VCP_3") (pintype "bidirectional"))
    )
    (net (code "103") (name "Net-(U4-CP1)") (class "Default")
      (node (ref "C37") (pin "2") (pinfunction "2_2") (pintype "passive"))
      (node (ref "U4") (pin "1") (pinfunction "CP1_1") (pintype "bidirectional"))
    )
    (net (code "104") (name "Net-(U4-CP2)") (class "Default")
      (node (ref "C37") (pin "1") (pinfunction "1_1") (pintype "passive"))
      (node (ref "U4") (pin "2") (pinfunction "CP2_2") (pintype "bidirectional"))
    )
    (net (code "105") (name "Net-(U4-ISENA)") (class "Default")
      (node (ref "R33") (pin "2") (pinfunction "2_2") (pintype "passive"))
      (node (ref "U4") (pin "6") (pinfunction "ISENA_6") (pintype "bidirectional"))
    )
    (net (code "106") (name "Net-(U4-ISENB)") (class "Default")
      (node (ref "R34") (pin "2") (pinfunction "2_2") (pintype "passive"))
      (node (ref "U4") (pin "9") (pinfunction "ISENB_9") (pintype "bidirectional"))
    )
    (net (code "107") (name "Net-(U4-MODE0)") (class "Default")
      (node (ref "JP4") (pin "5") (pinfunction "5_5") (pintype "passive"))
      (node (ref "U4") (pin "24") (pinfunction "MODE0_24") (pintype "input"))
    )
    (net (code "108") (name "Net-(U4-MODE1)") (class "Default")
      (node (ref "JP4") (pin "3") (pinfunction "3_3") (pintype "passive"))
      (node (ref "U4") (pin "25") (pinfunction "MODE1_25") (pintype "input"))
    )
    (net (code "109") (name "Net-(U4-MODE2)") (class "Default")
      (node (ref "JP4") (pin "1") (pinfunction "1_1") (pintype "passive"))
      (node (ref "U4") (pin "26") (pinfunction "MODE2_26") (pintype "input"))
    )
    (net (code "110") (name "Net-(U4-VCP)") (class "Default")
      (node (ref "C33") (pin "2") (pinfunction "2_2") (pintype "passive"))
      (node (ref "R35") (pin "2") (pinfunction "2_2") (pintype "passive"))
      (node (ref "U4") (pin "3") (pinfunction "VCP_3") (pintype "bidirectional"))
    )
    (net (code "111") (name "VCC") (class "Default")
      (node (ref "C16") (pin "2") (pinfunction "2_2") (pintype "passive"))
      (node (ref "C17") (pin "2") (pinfunction "2_2") (pintype "passive"))
      (node (ref "C21") (pin "1") (pinfunction "1_1") (pintype "passive"))
      (node (ref "C22") (pin "2") (pinfunction "2_2") (pintype "passive"))
      (node (ref "C23") (pin "2") (pinfunction "2_2") (pintype "passive"))
      (node (ref "C24") (pin "2") (pinfunction "2_2") (pintype "passive"))
      (node (ref "C27") (pin "1") (pinfunction "1_1") (pintype "passive"))
      (node (ref "C28") (pin "2") (pinfunction "2_2") (pintype "passive"))
      (node (ref "C29") (pin "2") (pinfunction "2_2") (pintype "passive"))
      (node (ref "C3") (pin "2") (pinfunction "2_2") (pintype "passive"))
      (node (ref "C30") (pin "2") (pinfunction "2_2") (pintype "passive"))
      (node (ref "C33") (pin "1") (pinfunction "1_1") (pintype "passive"))
      (node (ref "C34") (pin "2") (pinfunction "2_2") (pintype "passive"))
      (node (ref "C35") (pin "2") (pinfunction "2_2") (pintype "passive"))
      (node (ref "C36") (pin "2") (pinfunction "2_2") (pintype "passive"))
      (node (ref "C4") (pin "2") (pinfunction "2_2") (pintype "passive"))
      (node (ref "C5") (pin "2") (pinfunction "2_2") (pintype "passive"))
      (node (ref "C6") (pin "2") (pinfunction "2_2") (pintype "passive"))
      (node (ref "C7") (pin "1") (pinfunction "1_1") (pintype "passive"))
      (node (ref "C8") (pin "2") (pinfunction "2_2") (pintype "passive"))
      (node (ref "D1") (pin "C") (pinfunction "C_C") (pintype "passive"))
      (node (ref "D2") (pin "C") (pinfunction "C_C") (pintype "passive"))
      (node (ref "D3") (pin "C") (pinfunction "C_C") (pintype "passive"))
      (node (ref "D4") (pin "C") (pinfunction "C_C") (pintype "passive"))
      (node (ref "PWM1/2") (pin "1") (pinfunction "KL_1") (pintype "passive"))
      (node (ref "PWM1/2") (pin "3") (pinfunction "KL_3") (pintype "passive"))
      (node (ref "PWM3/4") (pin "1") (pinfunction "KL_1") (pintype "passive"))
      (node (ref "PWM3/4") (pin "3") (pinfunction "KL_3") (pintype "passive"))
      (node (ref "PWR") (pin "1") (pinfunction "KL_1") (pintype "passive"))
      (node (ref "PWR") (pin "3") (pinfunction "KL_3") (pintype "passive"))
      (node (ref "R26") (pin "1") (pinfunction "1_1") (pintype "passive"))
      (node (ref "R29") (pin "1") (pinfunction "1_1") (pintype "passive"))
      (node (ref "R32") (pin "1") (pinfunction "1_1") (pintype "passive"))
      (node (ref "R35") (pin "1") (pinfunction "1_1") (pintype "passive"))
      (node (ref "U1") (pin "11") (pinfunction "VMB_11") (pintype "power_in"))
      (node (ref "U1") (pin "4") (pinfunction "VMA_4") (pintype "power_in"))
      (node (ref "U2") (pin "11") (pinfunction "VMB_11") (pintype "power_in"))
      (node (ref "U2") (pin "4") (pinfunction "VMA_4") (pintype "power_in"))
      (node (ref "U3") (pin "11") (pinfunction "VMB_11") (pintype "power_in"))
      (node (ref "U3") (pin "4") (pinfunction "VMA_4") (pintype "power_in"))
      (node (ref "U4") (pin "11") (pinfunction "VMB_11") (pintype "power_in"))
      (node (ref "U4") (pin "4") (pinfunction "VMA_4") (pintype "power_in"))
    )
    (net (code "112") (name "unconnected-(INTERCON-Pad2)") (class "Default")
      (node (ref "INTERCON") (pin "2") (pinfunction "2_2") (pintype "passive"))
    )
    (net (code "113") (name "unconnected-(INTERCON-Pad4)") (class "Default")
      (node (ref "INTERCON") (pin "4") (pinfunction "4_4") (pintype "passive"))
    )
    (net (code "114") (name "unconnected-(U$1-AN2{slash}C2INB{slash}RP13{slash}CN4{slash}RB2-Pad23)") (class "Default")
      (node (ref "U$1") (pin "23") (pinfunction "AN2/C2INB/RP13/CN4/RB2_23") (pintype "bidirectional"))
    )
    (net (code "115") (name "unconnected-(U$1-AN3{slash}C2INA{slash}CN5{slash}RB3-Pad22)") (class "Default")
      (node (ref "U$1") (pin "22") (pinfunction "AN3/C2INA/CN5/RB3_22") (pintype "bidirectional"))
    )
    (net (code "116") (name "unconnected-(U$1-ASCL2{slash}RP136{slash}CN43{slash}RA14-Pad66)") (class "Default")
      (node (ref "U$1") (pin "66") (pinfunction "ASCL2/RP136/CN43/RA14_66") (pintype "bidirectional"))
    )
    (net (code "117") (name "unconnected-(U$1-ASDA2{slash}RP135{slash}CN44{slash}RA15-Pad67)") (class "Default")
      (node (ref "U$1") (pin "67") (pinfunction "ASDA2/RP135/CN44/RA15_67") (pintype "bidirectional"))
    )
    (net (code "118") (name "unconnected-(U$1-C2INC{slash}RP27{slash}CN11{slash}PMA2{slash}RG9-Pad14)") (class "Default")
      (node (ref "U$1") (pin "14") (pinfunction "C2INC/RP27/CN11/PMA2/RG9_14") (pintype "bidirectional"))
    )
    (net (code "119") (name "unconnected-(U$1-C2IND{slash}RP19{slash}CN10{slash}PMA3{slash}RG8-Pad12)") (class "Default")
      (node (ref "U$1") (pin "12") (pinfunction "C2IND/RP19/CN10/PMA3/RG8_12") (pintype "bidirectional"))
    )
    (net (code "120") (name "unconnected-(U$1-C3INB{slash}CN15{slash}RD6-Pad83)") (class "Default")
      (node (ref "U$1") (pin "83") (pinfunction "C3INB/CN15/RD6_83") (pintype "bidirectional"))
    )
    (net (code "121") (name "unconnected-(U$1-CN19{slash}RD13-Pad80)") (class "Default")
      (node (ref "U$1") (pin "80") (pinfunction "CN19/RD13_80") (pintype "bidirectional"))
    )
    (net (code "122") (name "unconnected-(U$1-CN63{slash}PMD5{slash}RE5-Pad3)") (class "Default")
      (node (ref "U$1") (pin "3") (pinfunction "CN63/PMD5/RE5_3") (pintype "bidirectional"))
    )
    (net (code "123") (name "unconnected-(U$1-CN68{slash}RF0-Pad87)") (class "Default")
      (node (ref "U$1") (pin "87") (pinfunction "CN68/RF0_87") (pintype "bidirectional"))
    )
    (net (code "124") (name "unconnected-(U$1-CN82{slash}RG15-Pad1)") (class "Default")
      (node (ref "U$1") (pin "1") (pinfunction "CN82/RG15_1") (pintype "bidirectional"))
    )
    (net (code "125") (name "unconnected-(U$1-PMBE{slash}RP22{slash}CN52{slash}RD3-Pad78)") (class "Default")
      (node (ref "U$1") (pin "78") (pinfunction "PMBE/RP22/CN52/RD3_78") (pintype "bidirectional"))
    )
    (net (code "126") (name "unconnected-(U$1-PMRD{slash}RP20{slash}CN14{slash}RD5-Pad82)") (class "Default")
      (node (ref "U$1") (pin "82") (pinfunction "PMRD/RP20/CN14/RD5_82") (pintype "bidirectional"))
    )
    (net (code "127") (name "unconnected-(U$1-PMWR{slash}RP25{slash}CN13{slash}RD4-Pad81)") (class "Default")
      (node (ref "U$1") (pin "81") (pinfunction "PMWR/RP25/CN13/RD4_81") (pintype "bidirectional"))
    )
    (net (code "128") (name "unconnected-(U$1-RP3{slash}CN55{slash}PMCS2{slash}RD10-Pad70)") (class "Default")
      (node (ref "U$1") (pin "70") (pinfunction "RP3/CN55/PMCS2/RD10_70") (pintype "bidirectional"))
    )
    (net (code "129") (name "unconnected-(U$1-RP4{slash}CN54{slash}RD9-Pad69)") (class "Default")
      (node (ref "U$1") (pin "69") (pinfunction "RP4/CN54/RD9_69") (pintype "bidirectional"))
    )
    (net (code "130") (name "unconnected-(U$1-RP5{slash}CN21{slash}RD15-Pad48)") (class "Default")
      (node (ref "U$1") (pin "48") (pinfunction "RP5/CN21/RD15_48") (pintype "bidirectional"))
    )
    (net (code "131") (name "unconnected-(U$1-RP10{slash}CN17{slash}PMA9{slash}RF4-Pad49)") (class "Default")
      (node (ref "U$1") (pin "49") (pinfunction "RP10/CN17/PMA9/RF4_49") (pintype "bidirectional"))
    )
    (net (code "132") (name "unconnected-(U$1-RP11{slash}CN49{slash}RD0-Pad72)") (class "Default")
      (node (ref "U$1") (pin "72") (pinfunction "RP11/CN49/RD0_72") (pintype "bidirectional"))
    )
    (net (code "133") (name "unconnected-(U$1-RP12{slash}CN56{slash}PMCS1{slash}RD11-Pad71)") (class "Default")
      (node (ref "U$1") (pin "71") (pinfunction "RP12/CN56/PMCS1/RD11_71") (pintype "bidirectional"))
    )
    (net (code "134") (name "unconnected-(U$1-RP23{slash}CN51{slash}RD2-Pad77)") (class "Default")
      (node (ref "U$1") (pin "77") (pinfunction "RP23/CN51/RD2_77") (pintype "bidirectional"))
    )
    (net (code "135") (name "unconnected-(U$1-RP24{slash}CN50{slash}RD1-Pad76)") (class "Default")
      (node (ref "U$1") (pin "76") (pinfunction "RP24/CN50/RD1_76") (pintype "bidirectional"))
    )
    (net (code "136") (name "unconnected-(U$1-RP138{slash}CN45{slash}RC1-Pad6)") (class "Default")
      (node (ref "U$1") (pin "6") (pinfunction "RP138/CN45/RC1_6") (pintype "bidirectional"))
    )
    (net (code "137") (name "unconnected-(U$1-RP139{slash}CN46{slash}RC2-Pad7)") (class "Default")
      (node (ref "U$1") (pin "7") (pinfunction "RP139/CN46/RC2_7") (pintype "bidirectional"))
    )
    (net (code "138") (name "unconnected-(U$1-RP140{slash}CN47{slash}RC3-Pad8)") (class "Default")
      (node (ref "U$1") (pin "8") (pinfunction "RP140/CN47/RC3_8") (pintype "bidirectional"))
    )
    (net (code "139") (name "unconnected-(U$1-RP141{slash}CN48{slash}RC4-Pad9)") (class "Default")
      (node (ref "U$1") (pin "9") (pinfunction "RP141/CN48/RC4_9") (pintype "bidirectional"))
    )
    (net (code "140") (name "unconnected-(U$1-RP143{slash}CN20{slash}RD14-Pad47)") (class "Default")
      (node (ref "U$1") (pin "47") (pinfunction "RP143/CN20/RD14_47") (pintype "bidirectional"))
    )
    (net (code "141") (name "unconnected-(U$1-RP144{slash}CN73{slash}RF7-Pad54)") (class "Default")
      (node (ref "U$1") (pin "54") (pinfunction "RP144/CN73/RF7_54") (pintype "bidirectional"))
    )
    (net (code "142") (name "unconnected-(U$1-RP145{slash}INT0{slash}CN72{slash}RF6-Pad55)") (class "Default")
      (node (ref "U$1") (pin "55") (pinfunction "RP145/INT0/CN72/RF6_55") (pintype "bidirectional"))
    )
    (net (code "143") (name "unconnected-(U$1-RPI42{slash}CN57{slash}RD12-Pad79)") (class "Default")
      (node (ref "U$1") (pin "79") (pinfunction "RPI42/CN57/RD12_79") (pintype "bidirectional"))
    )
    (net (code "144") (name "unconnected-(U$1-RTCC{slash}RP2{slash}CN53{slash}RD8-Pad68)") (class "Default")
      (node (ref "U$1") (pin "68") (pinfunction "RTCC/RP2/CN53/RD8_68") (pintype "bidirectional"))
    )
    (net (code "145") (name "unconnected-(U$1-SCL1{slash}CN83{slash}RG2-Pad57)") (class "Default")
      (node (ref "U$1") (pin "57") (pinfunction "SCL1/CN83/RG2_57") (pintype "bidirectional"))
    )
    (net (code "146") (name "unconnected-(U$1-SCL2{slash}CN35{slash}RA2-Pad58)") (class "Default")
      (node (ref "U$1") (pin "58") (pinfunction "SCL2/CN35/RA2_58") (pintype "bidirectional"))
    )
    (net (code "147") (name "unconnected-(U$1-SCL3{slash}CN64{slash}PMD6{slash}RE6-Pad4)") (class "Default")
      (node (ref "U$1") (pin "4") (pinfunction "SCL3/CN64/PMD6/RE6_4") (pintype "bidirectional"))
    )
    (net (code "148") (name "unconnected-(U$1-SDA1{slash}CN84{slash}RG3-Pad56)") (class "Default")
      (node (ref "U$1") (pin "56") (pinfunction "SDA1/CN84/RG3_56") (pintype "bidirectional"))
    )
    (net (code "149") (name "unconnected-(U$1-SDA2{slash}CN36{slash}RA3-Pad59)") (class "Default")
      (node (ref "U$1") (pin "59") (pinfunction "SDA2/CN36/RA3_59") (pintype "bidirectional"))
    )
    (net (code "150") (name "unconnected-(U$1-SDA3{slash}CN65{slash}PHD7{slash}RE7-Pad5)") (class "Default")
      (node (ref "U$1") (pin "5") (pinfunction "SDA3/CN65/PHD7/RE7_5") (pintype "bidirectional"))
    )
    (net (code "151") (name "unconnected-(U$1-SE{slash}C3INA{slash}CN16{slash}RD7-Pad84)") (class "Default")
      (node (ref "U$1") (pin "84") (pinfunction "SE/C3INA/CN16/RD7_84") (pintype "bidirectional"))
    )
    (net (code "152") (name "unconnected-(U$1-SOSCI{slash}C3IND{slash}CN1{slash}RC13-Pad73)") (class "Default")
      (node (ref "U$1") (pin "73") (pinfunction "SOSCI/C3IND/CN1/RC13_73") (pintype "bidirectional"))
    )
    (net (code "153") (name "unconnected-(U$1-SOSCO{slash}C3INC{slash}RP137{slash}CN0{slash}RC14-Pad74)") (class "Default")
      (node (ref "U$1") (pin "74") (pinfunction "SOSCO/C3INC/RP137/CN0/RC14_74") (pintype "bidirectional"))
    )
    (net (code "154") (name "unconnected-(U$1-TDI{slash}CN37{slash}RA4-Pad60)") (class "Default")
      (node (ref "U$1") (pin "60") (pinfunction "TDI/CN37/RA4_60") (pintype "bidirectional"))
    )
    (net (code "155") (name "unconnected-(U$1-TDO{slash}CN38{slash}RA5-Pad61)") (class "Default")
      (node (ref "U$1") (pin "61") (pinfunction "TDO/CN38/RA5_61") (pintype "bidirectional"))
    )
    (net (code "156") (name "unconnected-(U$1-TMS{slash}CN33{slash}RA0-Pad17)") (class "Default")
      (node (ref "U$1") (pin "17") (pinfunction "TMS/CN33/RA0_17") (pintype "bidirectional"))
    )
    (net (code "157") (name "unconnected-(U1-DECAY-Pad19)") (class "Default")
      (node (ref "U1") (pin "19") (pinfunction "DECAY_19") (pintype "input"))
    )
    (net (code "158") (name "unconnected-(U1-NC-Pad23)") (class "Default")
      (node (ref "U1") (pin "23") (pinfunction "NC_23") (pintype "no_connect"))
    )
    (net (code "159") (name "unconnected-(U1-NENBL-Pad21)") (class "Default")
      (node (ref "U1") (pin "21") (pinfunction "NENBL_21") (pintype "input"))
    )
    (net (code "160") (name "unconnected-(U1-NHOME-Pad27)") (class "Default")
      (node (ref "U1") (pin "27") (pinfunction "NHOME_27") (pintype "input"))
    )
    (net (code "161") (name "unconnected-(U1-NRESET-Pad16)") (class "Default")
      (node (ref "U1") (pin "16") (pinfunction "NRESET_16") (pintype "input"))
    )
    (net (code "162") (name "unconnected-(U2-DECAY-Pad19)") (class "Default")
      (node (ref "U2") (pin "19") (pinfunction "DECAY_19") (pintype "input"))
    )
    (net (code "163") (name "unconnected-(U2-NC-Pad23)") (class "Default")
      (node (ref "U2") (pin "23") (pinfunction "NC_23") (pintype "no_connect"))
    )
    (net (code "164") (name "unconnected-(U2-NENBL-Pad21)") (class "Default")
      (node (ref "U2") (pin "21") (pinfunction "NENBL_21") (pintype "input"))
    )
    (net (code "165") (name "unconnected-(U2-NHOME-Pad27)") (class "Default")
      (node (ref "U2") (pin "27") (pinfunction "NHOME_27") (pintype "input"))
    )
    (net (code "166") (name "unconnected-(U2-NRESET-Pad16)") (class "Default")
      (node (ref "U2") (pin "16") (pinfunction "NRESET_16") (pintype "input"))
    )
    (net (code "167") (name "unconnected-(U3-DECAY-Pad19)") (class "Default")
      (node (ref "U3") (pin "19") (pinfunction "DECAY_19") (pintype "input"))
    )
    (net (code "168") (name "unconnected-(U3-NC-Pad23)") (class "Default")
      (node (ref "U3") (pin "23") (pinfunction "NC_23") (pintype "no_connect"))
    )
    (net (code "169") (name "unconnected-(U3-NENBL-Pad21)") (class "Default")
      (node (ref "U3") (pin "21") (pinfunction "NENBL_21") (pintype "input"))
    )
    (net (code "170") (name "unconnected-(U3-NHOME-Pad27)") (class "Default")
      (node (ref "U3") (pin "27") (pinfunction "NHOME_27") (pintype "input"))
    )
    (net (code "171") (name "unconnected-(U3-NRESET-Pad16)") (class "Default")
      (node (ref "U3") (pin "16") (pinfunction "NRESET_16") (pintype "input"))
    )
    (net (code "172") (name "unconnected-(U4-DECAY-Pad19)") (class "Default")
      (node (ref "U4") (pin "19") (pinfunction "DECAY_19") (pintype "input"))
    )
    (net (code "173") (name "unconnected-(U4-NC-Pad23)") (class "Default")
      (node (ref "U4") (pin "23") (pinfunction "NC_23") (pintype "no_connect"))
    )
    (net (code "174") (name "unconnected-(U4-NENBL-Pad21)") (class "Default")
      (node (ref "U4") (pin "21") (pinfunction "NENBL_21") (pintype "input"))
    )
    (net (code "175") (name "unconnected-(U4-NHOME-Pad27)") (class "Default")
      (node (ref "U4") (pin "27") (pinfunction "NHOME_27") (pintype "input"))
    )
    (net (code "176") (name "unconnected-(U4-NRESET-Pad16)") (class "Default")
      (node (ref "U4") (pin "16") (pinfunction "NRESET_16") (pintype "input"))
    )
  )
)
